# VFD_Ura_Display.net
KiCad netlist of a schematic drawn in Altium Designer
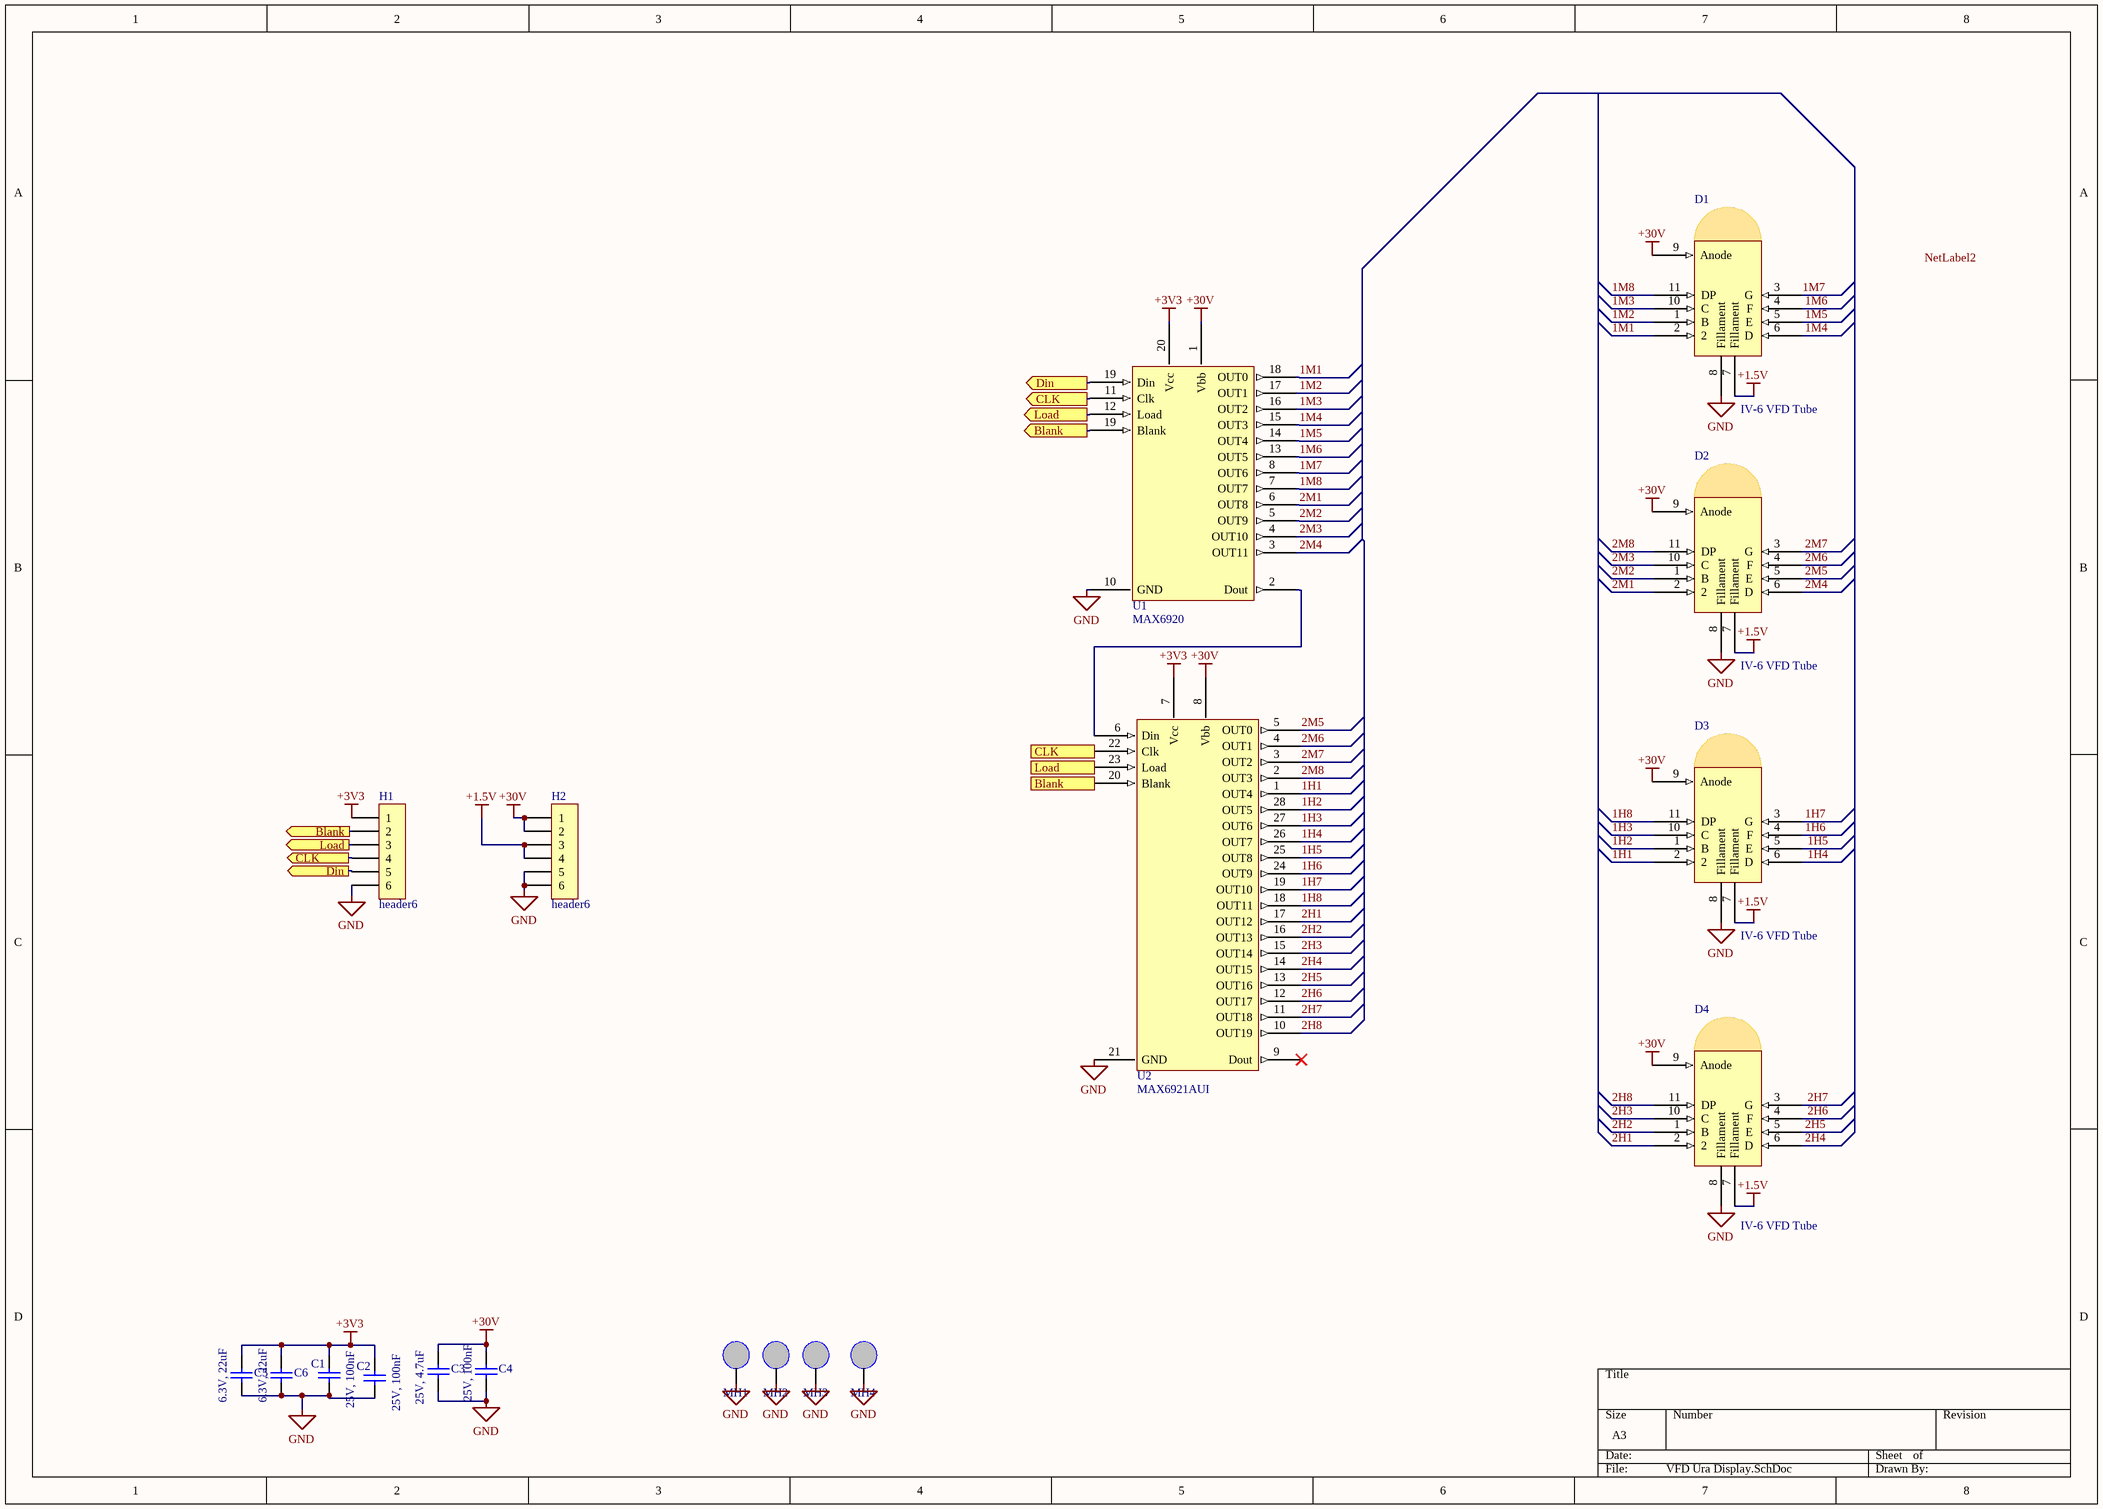
[diagram p0: VFD Ura Display.SchDoc]

(export (version "E")
  (design (tool "Eeschema 10.0.6"))
  (components
    (comp (ref "C1")
      (value "25V, 100nF")
      (footprint "0603_1.6x0.8x0.8mm_Reflow Soldering")
      (description "WCAP-CSGP Ceramic Capacitors, 0603, X7R, 25V, 100nF")
      (fields (field (name "PART NUMBER") "885012206071") (field (name "PUBLISHER") "Wurth Elektronik"))
      (libsource (lib "ALTIUM-WCAP-CSGP-0603-rev17b") (part "885012206071"))
    )
    (comp (ref "C2")
      (value "25V, 100nF")
      (footprint "0603_1.6x0.8x0.8mm_Reflow Soldering")
      (description "WCAP-CSGP Ceramic Capacitors, 0603, X7R, 25V, 100nF")
      (fields (field (name "PART NUMBER") "885012206071") (field (name "PUBLISHER") "Wurth Elektronik"))
      (libsource (lib "ALTIUM-WCAP-CSGP-0603-rev17b") (part "885012206071"))
    )
    (comp (ref "C3")
      (value "25V, 4.7uF")
      (footprint "0805_2x1.25x1.25mm_Reflow Soldering")
      (description "WCAP-CSGP Ceramic Capacitors, 0805, X5R, 25V, 4.7uF")
      (fields (field (name "PART NUMBER") "885012107018") (field (name "PUBLISHER") "Wurth Elektronik"))
      (libsource (lib "ALTIUM-WCAP-CSGP-0805-rev17b") (part "885012107018"))
    )
    (comp (ref "C4")
      (value "25V, 100nF")
      (footprint "0603_1.6x0.8x0.8mm_Reflow Soldering")
      (description "WCAP-CSGP Ceramic Capacitors, 0603, X7R, 25V, 100nF")
      (fields (field (name "PART NUMBER") "885012206071") (field (name "PUBLISHER") "Wurth Elektronik"))
      (libsource (lib "ALTIUM-WCAP-CSGP-0603-rev17b") (part "885012206071"))
    )
    (comp (ref "C5")
      (value "6.3V, 22uF")
      (footprint "0805_2x1.25x1.25mm_Reflow Soldering")
      (description "WCAP-CSGP Ceramic Capacitors, 0805, X5R, 6.3V, 22uF")
      (fields (field (name "PART NUMBER") "885012107005") (field (name "PUBLISHER") "Wurth Elektronik"))
      (libsource (lib "ALTIUM-WCAP-CSGP-0805-rev17b") (part "885012107005"))
    )
    (comp (ref "C6")
      (value "6.3V, 22uF")
      (footprint "0805_2x1.25x1.25mm_Reflow Soldering")
      (description "WCAP-CSGP Ceramic Capacitors, 0805, X5R, 6.3V, 22uF")
      (fields (field (name "PART NUMBER") "885012107005") (field (name "PUBLISHER") "Wurth Elektronik"))
      (libsource (lib "ALTIUM-WCAP-CSGP-0805-rev17b") (part "885012107005"))
    )
    (comp (ref "D1") (value "IV-6 VFD Tube") (footprint "IV-6") (libsource (lib "IV-6") (part "IV-6")))
    (comp (ref "D2") (value "IV-6 VFD Tube") (footprint "IV-6") (libsource (lib "IV-6") (part "IV-6")))
    (comp (ref "D3") (value "IV-6 VFD Tube") (footprint "IV-6") (libsource (lib "IV-6") (part "IV-6")))
    (comp (ref "D4") (value "IV-6 VFD Tube") (footprint "IV-6") (libsource (lib "IV-6") (part "IV-6")))
    (comp (ref "H1") (value "header6") (footprint "Letev6") (libsource (lib "VolkD3D") (part "header6")))
    (comp (ref "H2") (value "header6") (footprint "Letev6") (libsource (lib "VolkD3D") (part "header6")))
    (comp (ref "MH1")
      (value "Mounting Hole M3")
      (footprint "Mounting Hole M3")
      (libsource (lib "Oblak Library") (part "Mounting Hole M3"))
    )
    (comp (ref "MH2")
      (value "Mounting Hole M3")
      (footprint "Mounting Hole M3")
      (libsource (lib "Oblak Library") (part "Mounting Hole M3"))
    )
    (comp (ref "MH3")
      (value "Mounting Hole M3")
      (footprint "Mounting Hole M3")
      (libsource (lib "Oblak Library") (part "Mounting Hole M3"))
    )
    (comp (ref "MH4")
      (value "Mounting Hole M3")
      (footprint "Mounting Hole M3")
      (libsource (lib "Oblak Library") (part "Mounting Hole M3"))
    )
    (comp (ref "U1")
      (value "MAX6920")
      (footprint "SO20 Wide")
      (libsource (lib "Oblak Library") (part "MAX6920"))
    )
    (comp (ref "U2") (value "MAX6921AUI") (footprint "TSOP 28") (libsource (lib "IV-6") (part "MAX6921AUI")))
  )
  (nets
    (net (code "1") (name "+1.5V") (class "Default")
      (node (ref "D1") (pin "7") (pinfunction "Fillament_7") (pintype "power_in"))
      (node (ref "D2") (pin "7") (pinfunction "Fillament_7") (pintype "power_in"))
      (node (ref "D3") (pin "7") (pinfunction "Fillament_7") (pintype "power_in"))
      (node (ref "D4") (pin "7") (pinfunction "Fillament_7") (pintype "power_in"))
      (node (ref "H2") (pin "3") (pinfunction "3_3") (pintype "passive"))
      (node (ref "H2") (pin "4") (pinfunction "4_4") (pintype "passive"))
    )
    (net (code "2") (name "+3V3") (class "Default")
      (node (ref "C1") (pin "2") (pinfunction "2_2") (pintype "passive"))
      (node (ref "C2") (pin "2") (pinfunction "2_2") (pintype "passive"))
      (node (ref "C5") (pin "2") (pinfunction "2_2") (pintype "passive"))
      (node (ref "C6") (pin "2") (pinfunction "2_2") (pintype "passive"))
      (node (ref "H1") (pin "1") (pinfunction "1_1") (pintype "passive"))
      (node (ref "U1") (pin "20") (pinfunction "Vcc_20") (pintype "power_in"))
      (node (ref "U2") (pin "7") (pinfunction "Vcc_7") (pintype "power_in"))
    )
    (net (code "3") (name "+30V") (class "Default")
      (node (ref "C3") (pin "2") (pinfunction "2_2") (pintype "passive"))
      (node (ref "C4") (pin "2") (pinfunction "2_2") (pintype "passive"))
      (node (ref "D1") (pin "9") (pinfunction "Anode_9") (pintype "input"))
      (node (ref "D2") (pin "9") (pinfunction "Anode_9") (pintype "input"))
      (node (ref "D3") (pin "9") (pinfunction "Anode_9") (pintype "input"))
      (node (ref "D4") (pin "9") (pinfunction "Anode_9") (pintype "input"))
      (node (ref "H2") (pin "1") (pinfunction "1_1") (pintype "passive"))
      (node (ref "H2") (pin "2") (pinfunction "2_2") (pintype "passive"))
      (node (ref "U1") (pin "1") (pinfunction "Vbb_1") (pintype "power_in"))
      (node (ref "U2") (pin "8") (pinfunction "Vbb_8") (pintype "power_in"))
    )
    (net (code "4") (name "/1H1") (class "Default")
      (node (ref "D3") (pin "2") (pinfunction "2_2") (pintype "input"))
      (node (ref "U2") (pin "1") (pinfunction "OUT4_1") (pintype "output"))
    )
    (net (code "5") (name "/1H2") (class "Default")
      (node (ref "D3") (pin "1") (pinfunction "B_1") (pintype "input"))
      (node (ref "U2") (pin "28") (pinfunction "OUT5_28") (pintype "output"))
    )
    (net (code "6") (name "/1H3") (class "Default")
      (node (ref "D3") (pin "10") (pinfunction "C_10") (pintype "input"))
      (node (ref "U2") (pin "27") (pinfunction "OUT6_27") (pintype "output"))
    )
    (net (code "7") (name "/1H4") (class "Default")
      (node (ref "D3") (pin "6") (pinfunction "D_6") (pintype "input"))
      (node (ref "U2") (pin "26") (pinfunction "OUT7_26") (pintype "output"))
    )
    (net (code "8") (name "/1H5") (class "Default")
      (node (ref "D3") (pin "5") (pinfunction "E_5") (pintype "input"))
      (node (ref "U2") (pin "25") (pinfunction "OUT8_25") (pintype "output"))
    )
    (net (code "9") (name "/1H6") (class "Default")
      (node (ref "D3") (pin "4") (pinfunction "F_4") (pintype "input"))
      (node (ref "U2") (pin "24") (pinfunction "OUT9_24") (pintype "output"))
    )
    (net (code "10") (name "/1H7") (class "Default")
      (node (ref "D3") (pin "3") (pinfunction "G_3") (pintype "input"))
      (node (ref "U2") (pin "19") (pinfunction "OUT10_19") (pintype "output"))
    )
    (net (code "11") (name "/1H8") (class "Default")
      (node (ref "D3") (pin "11") (pinfunction "DP_11") (pintype "input"))
      (node (ref "U2") (pin "18") (pinfunction "OUT11_18") (pintype "output"))
    )
    (net (code "12") (name "/1M1") (class "Default")
      (node (ref "D1") (pin "2") (pinfunction "2_2") (pintype "input"))
      (node (ref "U1") (pin "18") (pinfunction "OUT0_18") (pintype "output"))
    )
    (net (code "13") (name "/1M2") (class "Default")
      (node (ref "D1") (pin "1") (pinfunction "B_1") (pintype "input"))
      (node (ref "U1") (pin "17") (pinfunction "OUT1_17") (pintype "output"))
    )
    (net (code "14") (name "/1M3") (class "Default")
      (node (ref "D1") (pin "10") (pinfunction "C_10") (pintype "input"))
      (node (ref "U1") (pin "16") (pinfunction "OUT2_16") (pintype "output"))
    )
    (net (code "15") (name "/1M4") (class "Default")
      (node (ref "D1") (pin "6") (pinfunction "D_6") (pintype "input"))
      (node (ref "U1") (pin "15") (pinfunction "OUT3_15") (pintype "output"))
    )
    (net (code "16") (name "/1M5") (class "Default")
      (node (ref "D1") (pin "5") (pinfunction "E_5") (pintype "input"))
      (node (ref "U1") (pin "14") (pinfunction "OUT4_14") (pintype "output"))
    )
    (net (code "17") (name "/1M6") (class "Default")
      (node (ref "D1") (pin "4") (pinfunction "F_4") (pintype "input"))
      (node (ref "U1") (pin "13") (pinfunction "OUT5_13") (pintype "output"))
    )
    (net (code "18") (name "/1M7") (class "Default")
      (node (ref "D1") (pin "3") (pinfunction "G_3") (pintype "input"))
      (node (ref "U1") (pin "8") (pinfunction "OUT6_8") (pintype "output"))
    )
    (net (code "19") (name "/1M8") (class "Default")
      (node (ref "D1") (pin "11") (pinfunction "DP_11") (pintype "input"))
      (node (ref "U1") (pin "7") (pinfunction "OUT7_7") (pintype "output"))
    )
    (net (code "20") (name "/2H1") (class "Default")
      (node (ref "D4") (pin "2") (pinfunction "2_2") (pintype "input"))
      (node (ref "U2") (pin "17") (pinfunction "OUT12_17") (pintype "output"))
    )
    (net (code "21") (name "/2H2") (class "Default")
      (node (ref "D4") (pin "1") (pinfunction "B_1") (pintype "input"))
      (node (ref "U2") (pin "16") (pinfunction "OUT13_16") (pintype "output"))
    )
    (net (code "22") (name "/2H3") (class "Default")
      (node (ref "D4") (pin "10") (pinfunction "C_10") (pintype "input"))
      (node (ref "U2") (pin "15") (pinfunction "OUT14_15") (pintype "output"))
    )
    (net (code "23") (name "/2H4") (class "Default")
      (node (ref "D4") (pin "6") (pinfunction "D_6") (pintype "input"))
      (node (ref "U2") (pin "14") (pinfunction "OUT15_14") (pintype "output"))
    )
    (net (code "24") (name "/2H5") (class "Default")
      (node (ref "D4") (pin "5") (pinfunction "E_5") (pintype "input"))
      (node (ref "U2") (pin "13") (pinfunction "OUT16_13") (pintype "output"))
    )
    (net (code "25") (name "/2H6") (class "Default")
      (node (ref "D4") (pin "4") (pinfunction "F_4") (pintype "input"))
      (node (ref "U2") (pin "12") (pinfunction "OUT17_12") (pintype "output"))
    )
    (net (code "26") (name "/2H7") (class "Default")
      (node (ref "D4") (pin "3") (pinfunction "G_3") (pintype "input"))
      (node (ref "U2") (pin "11") (pinfunction "OUT18_11") (pintype "output"))
    )
    (net (code "27") (name "/2H8") (class "Default")
      (node (ref "D4") (pin "11") (pinfunction "DP_11") (pintype "input"))
      (node (ref "U2") (pin "10") (pinfunction "OUT19_10") (pintype "output"))
    )
    (net (code "28") (name "/2M1") (class "Default")
      (node (ref "D2") (pin "2") (pinfunction "2_2") (pintype "input"))
      (node (ref "U1") (pin "6") (pinfunction "OUT8_6") (pintype "output"))
    )
    (net (code "29") (name "/2M2") (class "Default")
      (node (ref "D2") (pin "1") (pinfunction "B_1") (pintype "input"))
      (node (ref "U1") (pin "5") (pinfunction "OUT9_5") (pintype "output"))
    )
    (net (code "30") (name "/2M3") (class "Default")
      (node (ref "D2") (pin "10") (pinfunction "C_10") (pintype "input"))
      (node (ref "U1") (pin "4") (pinfunction "OUT10_4") (pintype "output"))
    )
    (net (code "31") (name "/2M4") (class "Default")
      (node (ref "D2") (pin "6") (pinfunction "D_6") (pintype "input"))
      (node (ref "U1") (pin "3") (pinfunction "OUT11_3") (pintype "output"))
    )
    (net (code "32") (name "/2M5") (class "Default")
      (node (ref "D2") (pin "5") (pinfunction "E_5") (pintype "input"))
      (node (ref "U2") (pin "5") (pinfunction "OUT0_5") (pintype "output"))
    )
    (net (code "33") (name "/2M6") (class "Default")
      (node (ref "D2") (pin "4") (pinfunction "F_4") (pintype "input"))
      (node (ref "U2") (pin "4") (pinfunction "OUT1_4") (pintype "output"))
    )
    (net (code "34") (name "/2M7") (class "Default")
      (node (ref "D2") (pin "3") (pinfunction "G_3") (pintype "input"))
      (node (ref "U2") (pin "3") (pinfunction "OUT2_3") (pintype "output"))
    )
    (net (code "35") (name "/2M8") (class "Default")
      (node (ref "D2") (pin "11") (pinfunction "DP_11") (pintype "input"))
      (node (ref "U2") (pin "2") (pinfunction "OUT3_2") (pintype "output"))
    )
    (net (code "36") (name "/Blank") (class "Default")
      (node (ref "H1") (pin "2") (pinfunction "2_2") (pintype "passive"))
      (node (ref "U1") (pin "19") (pinfunction "Blank_19") (pintype "input"))
      (node (ref "U2") (pin "20") (pinfunction "Blank_20") (pintype "input"))
    )
    (net (code "37") (name "/CLK") (class "Default")
      (node (ref "H1") (pin "4") (pinfunction "4_4") (pintype "passive"))
      (node (ref "U1") (pin "11") (pinfunction "Clk_11") (pintype "input"))
      (node (ref "U2") (pin "22") (pinfunction "Clk_22") (pintype "input"))
    )
    (net (code "38") (name "/Din") (class "Default")
      (node (ref "H1") (pin "5") (pinfunction "5_5") (pintype "passive"))
      (node (ref "U1") (pin "19") (pinfunction "Din_19") (pintype "input"))
    )
    (net (code "39") (name "/Load") (class "Default")
      (node (ref "H1") (pin "3") (pinfunction "3_3") (pintype "passive"))
      (node (ref "U1") (pin "12") (pinfunction "Load_12") (pintype "input"))
      (node (ref "U2") (pin "23") (pinfunction "Load_23") (pintype "input"))
    )
    (net (code "41") (name "GND") (class "Default")
      (node (ref "C1") (pin "1") (pinfunction "1_1") (pintype "passive"))
      (node (ref "C2") (pin "1") (pinfunction "1_1") (pintype "passive"))
      (node (ref "C3") (pin "1") (pinfunction "1_1") (pintype "passive"))
      (node (ref "C4") (pin "1") (pinfunction "1_1") (pintype "passive"))
      (node (ref "C5") (pin "1") (pinfunction "1_1") (pintype "passive"))
      (node (ref "C6") (pin "1") (pinfunction "1_1") (pintype "passive"))
      (node (ref "D1") (pin "8") (pinfunction "Fillament_8") (pintype "power_in"))
      (node (ref "D2") (pin "8") (pinfunction "Fillament_8") (pintype "power_in"))
      (node (ref "D3") (pin "8") (pinfunction "Fillament_8") (pintype "power_in"))
      (node (ref "D4") (pin "8") (pinfunction "Fillament_8") (pintype "power_in"))
      (node (ref "H1") (pin "6") (pinfunction "6_6") (pintype "passive"))
      (node (ref "H2") (pin "5") (pinfunction "5_5") (pintype "passive"))
      (node (ref "H2") (pin "6") (pinfunction "6_6") (pintype "passive"))
      (node (ref "MH1") (pin "1") (pintype "passive"))
      (node (ref "MH2") (pin "1") (pintype "passive"))
      (node (ref "MH3") (pin "1") (pintype "passive"))
      (node (ref "MH4") (pin "1") (pintype "passive"))
      (node (ref "U1") (pin "10") (pinfunction "GND_10") (pintype "power_in"))
      (node (ref "U2") (pin "21") (pinfunction "GND_21") (pintype "power_in"))
    )
    (net (code "42") (name "Net-(U1-Dout)") (class "Default")
      (node (ref "U1") (pin "2") (pinfunction "Dout_2") (pintype "output"))
      (node (ref "U2") (pin "6") (pinfunction "Din_6") (pintype "input"))
    )
    (net (code "43") (name "unconnected-(U2-Dout-Pad9)") (class "Default")
      (node (ref "U2") (pin "9") (pinfunction "Dout_9") (pintype "output+no_connect"))
    )
  )
)
